# expansion_rxtx_rev_b.net
KiCad netlist of a schematic drawn in EAGLE
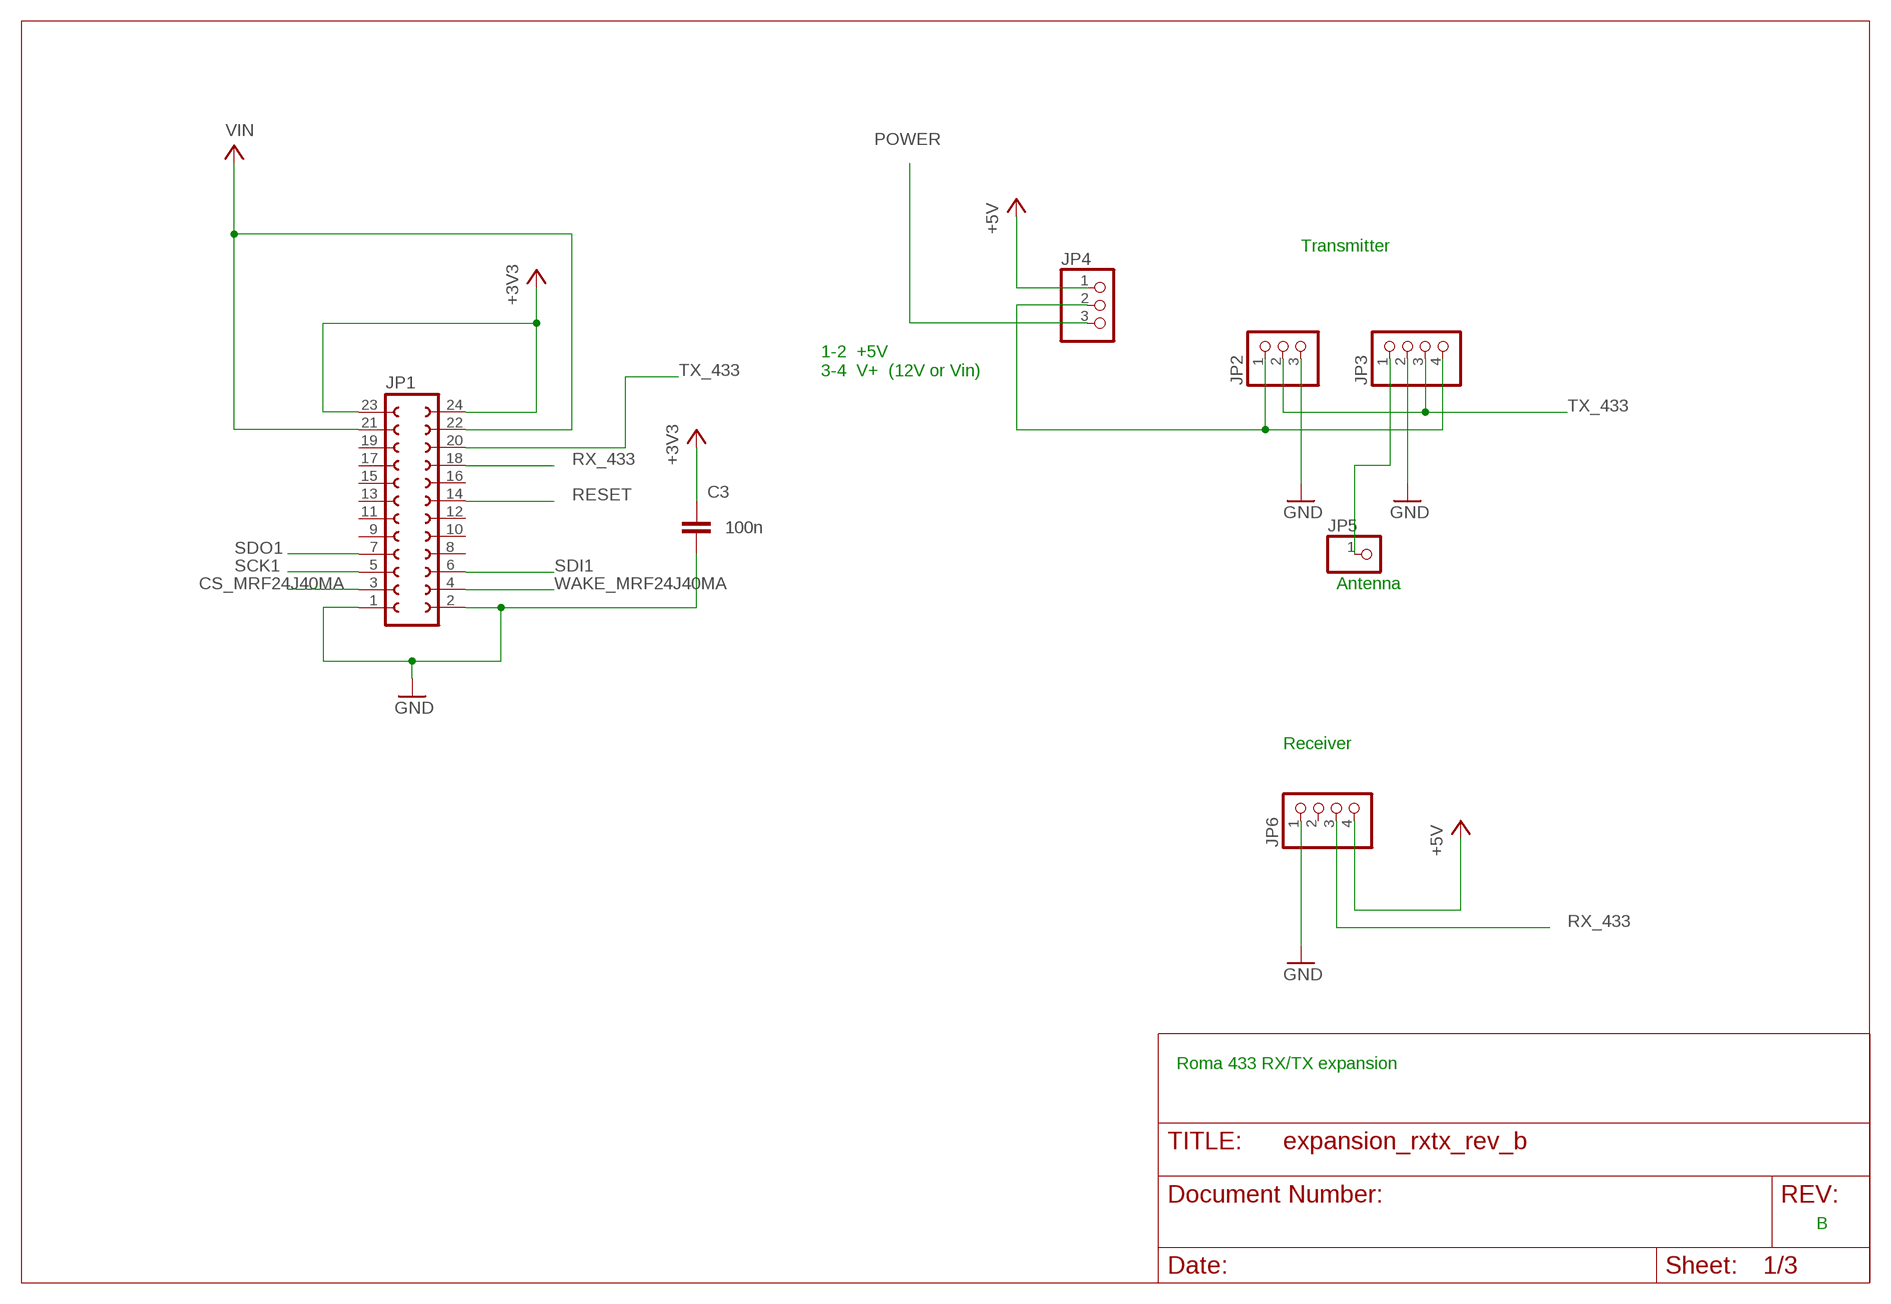
[diagram p0: schematic, sheet 1]
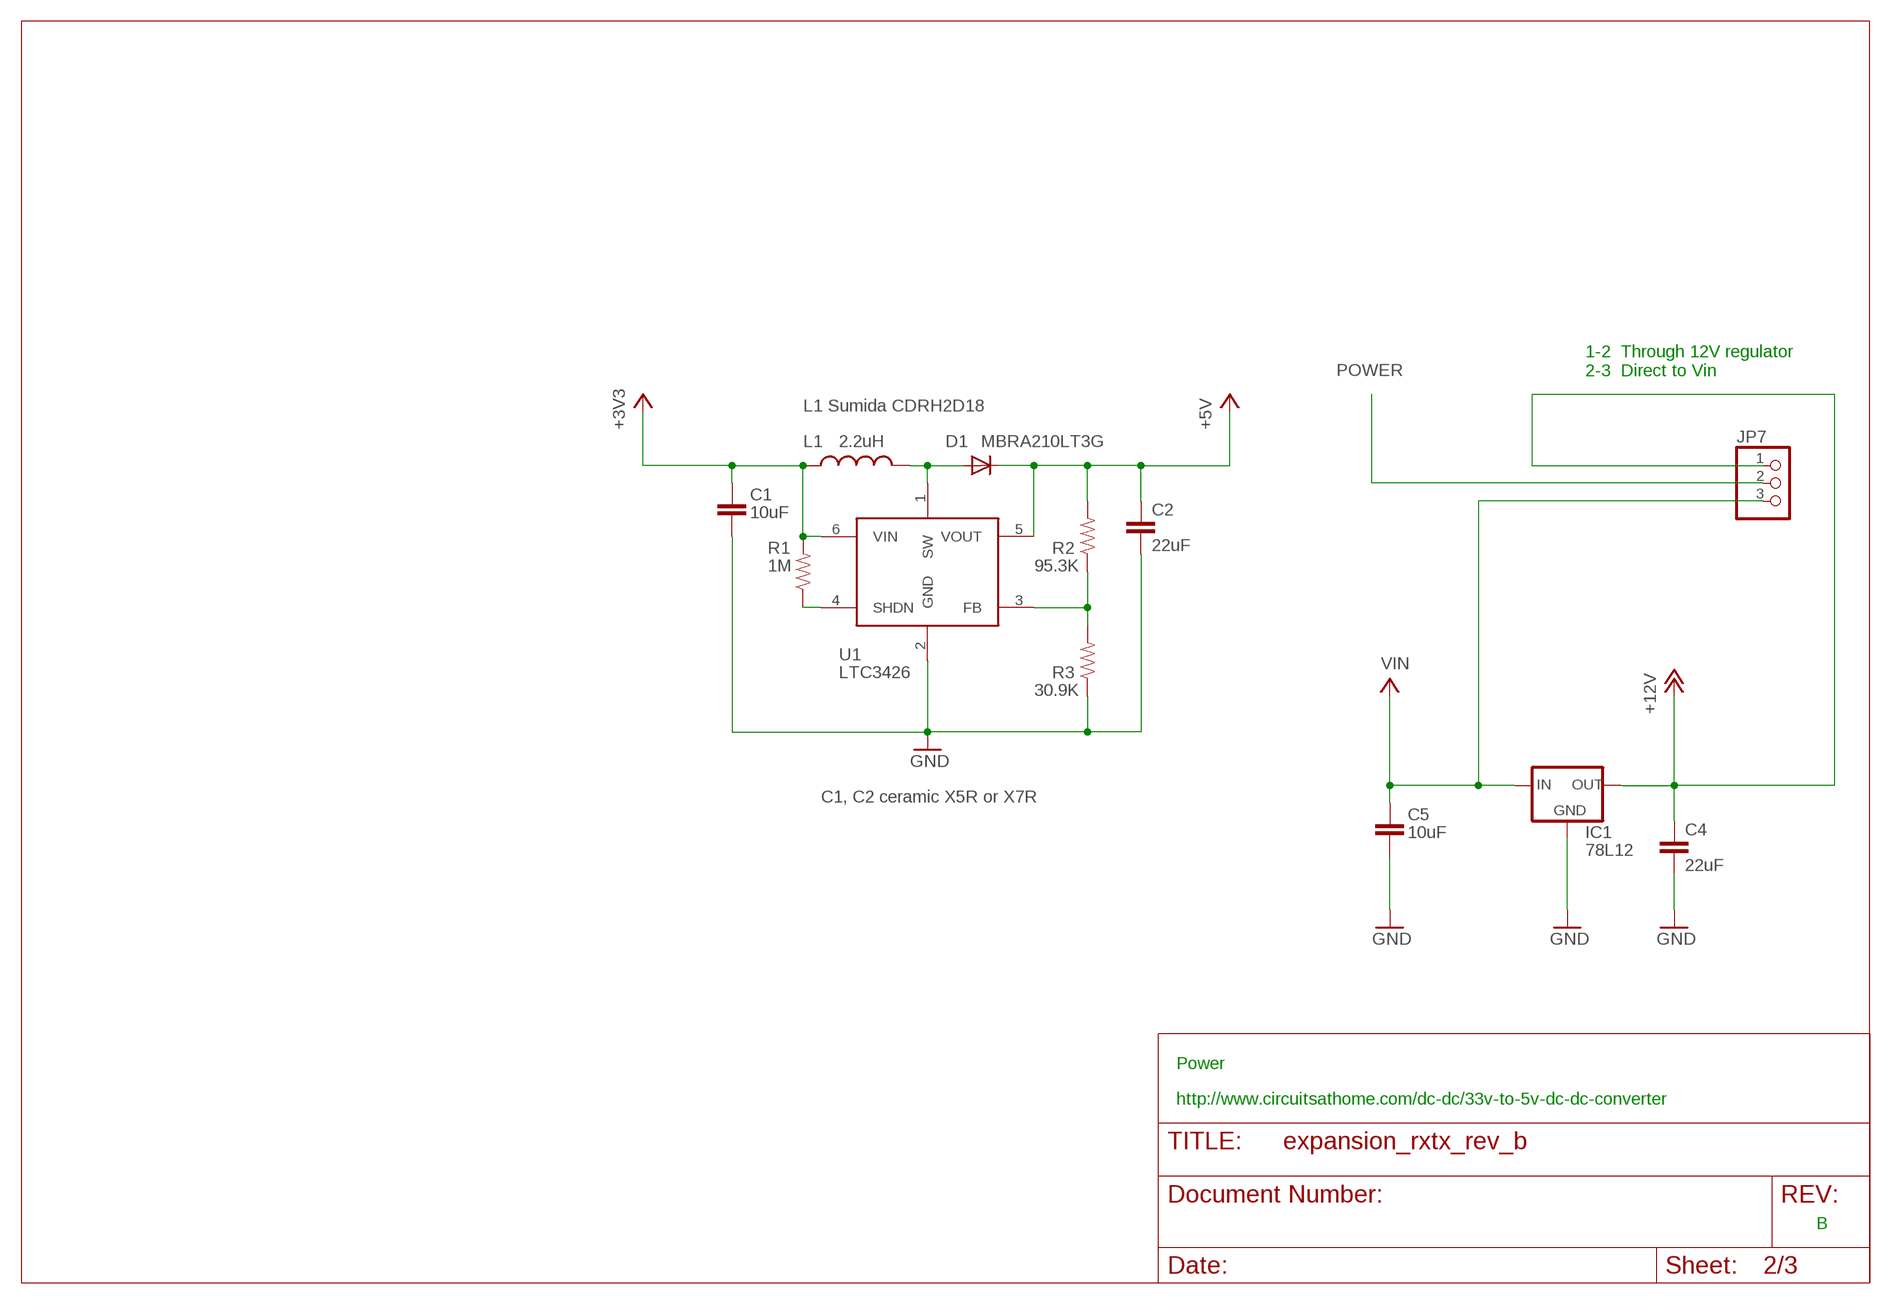
[diagram p1: schematic, sheet 2]
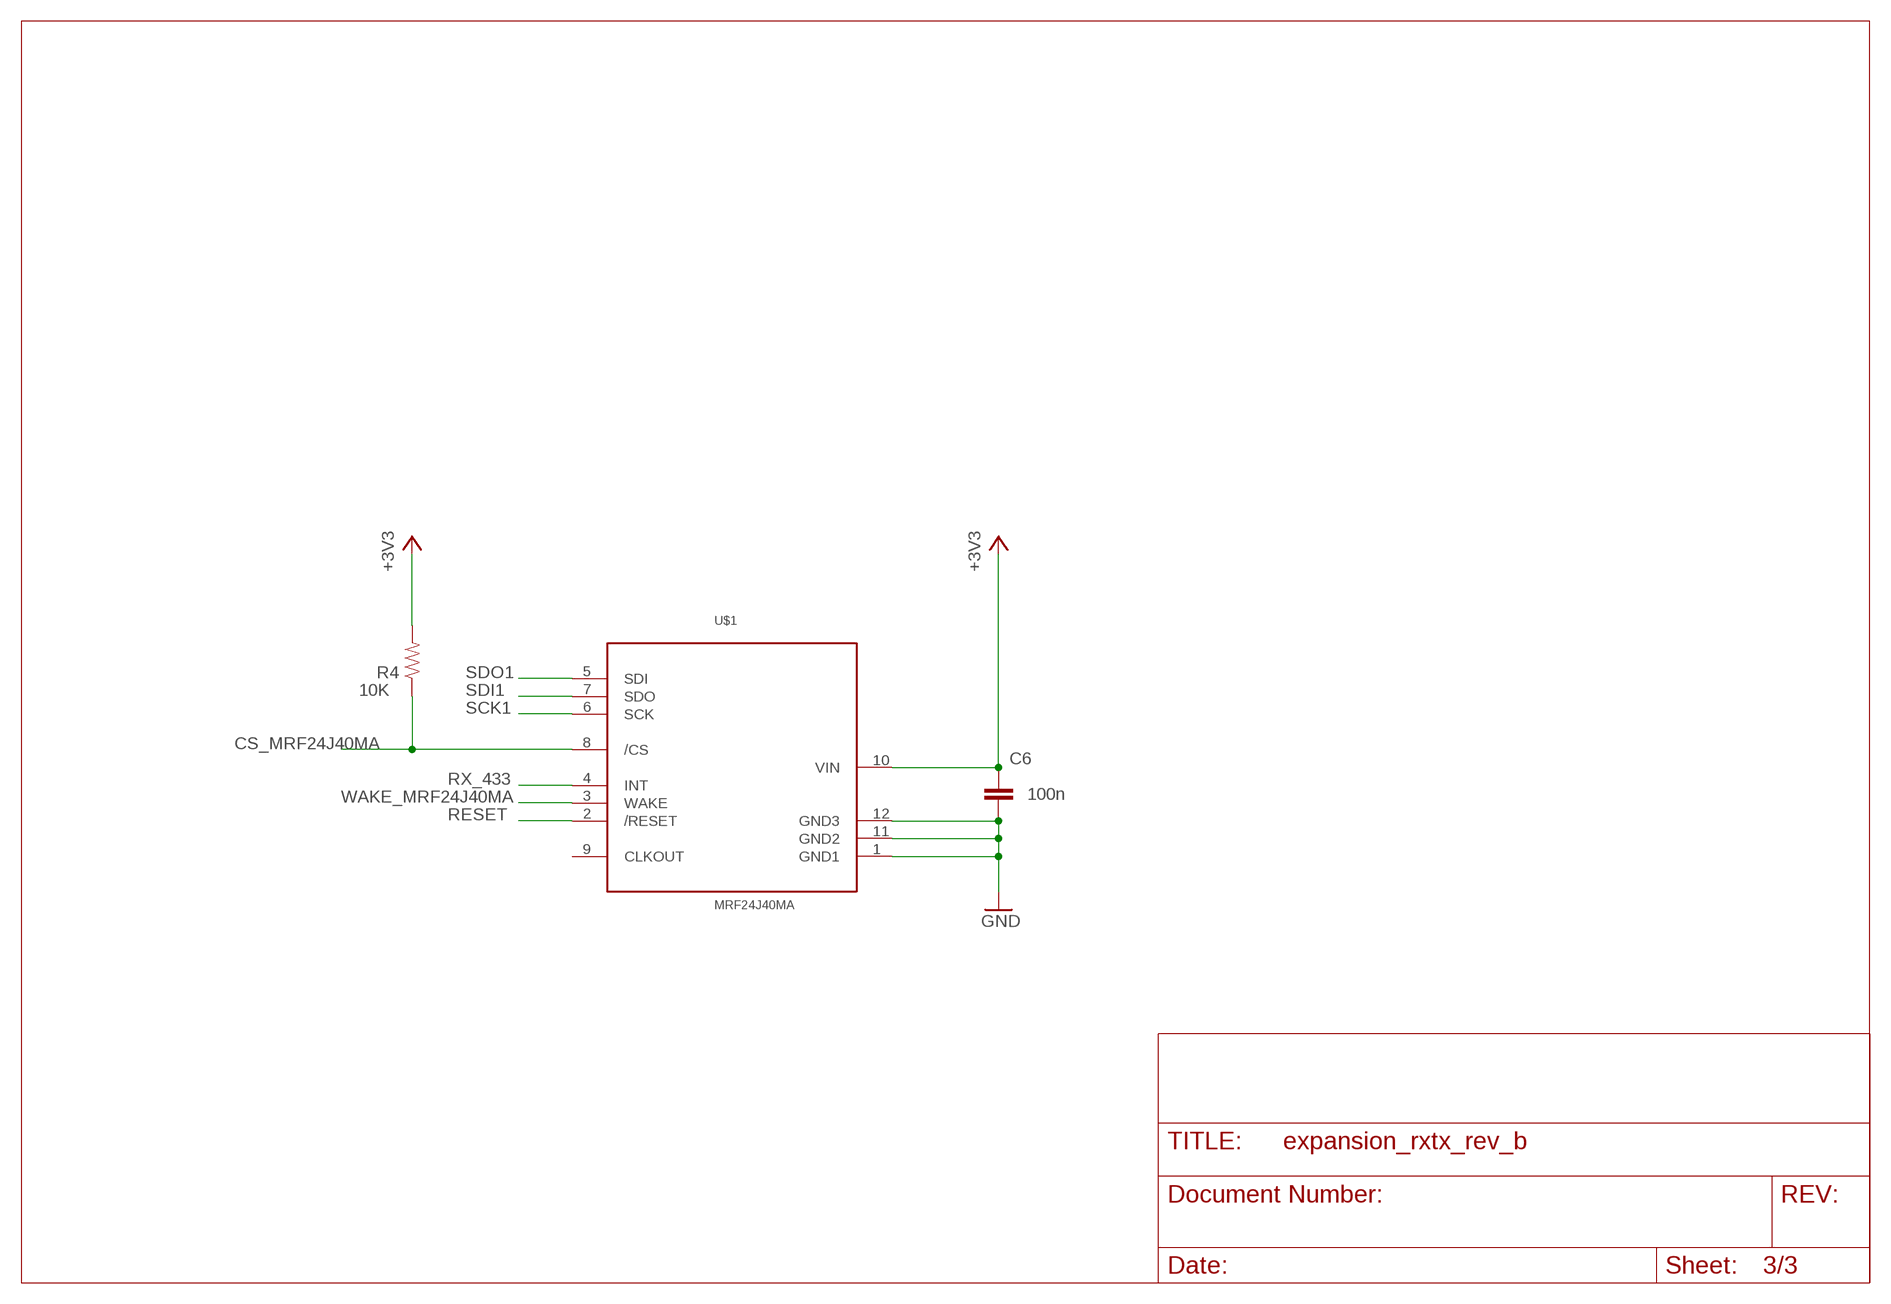
[diagram p2: schematic, sheet 3]

(export (version "E")
  (design (tool "Eeschema 10.0.6"))
  (components
    (comp (ref "C1")
      (value "10uF")
      (footprint "eagle-import:1210")
      (libsource (lib "eagle-import") (part "CAP1210"))
    )
    (comp (ref "C2")
      (value "22uF")
      (footprint "eagle-import:1210")
      (libsource (lib "eagle-import") (part "CAP1210"))
    )
    (comp (ref "C4")
      (value "22uF")
      (footprint "eagle-import:1210")
      (libsource (lib "eagle-import") (part "CAP1210"))
    )
    (comp (ref "C5")
      (value "10uF")
      (footprint "eagle-import:1210")
      (libsource (lib "eagle-import") (part "CAP1210"))
    )
    (comp (ref "D1")
      (value "MBRA210LT3G")
      (footprint "eagle-import:SMA-DIODE")
      (libsource (lib "eagle-import") (part "DIODESMA"))
    )
    (comp (ref "IC1")
      (value "78L12")
      (footprint "eagle-import:78LXX")
      (libsource (lib "eagle-import") (part "78LXX"))
    )
    (comp (ref "JP7")
      (value "PINHD-1X3")
      (footprint "eagle-import:1X03")
      (libsource (lib "eagle-import") (part "PINHD-1X3"))
    )
    (comp (ref "L1")
      (value "2.2uH")
      (footprint "eagle-import:1_3X1_3")
      (libsource (lib "eagle-import") (part "INDUCTOR1313"))
    )
    (comp (ref "R1")
      (value "1M")
      (footprint "eagle-import:0805")
      (libsource (lib "eagle-import") (part "RESISTOR0805"))
    )
    (comp (ref "R2")
      (value "95.3K")
      (footprint "eagle-import:0805")
      (libsource (lib "eagle-import") (part "RESISTOR0805"))
    )
    (comp (ref "R3")
      (value "30.9K")
      (footprint "eagle-import:0805")
      (libsource (lib "eagle-import") (part "RESISTOR0805"))
    )
    (comp (ref "U1")
      (value "LTC3426")
      (footprint "eagle-import:SOT23-6")
      (libsource (lib "eagle-import") (part "LTC3426"))
    )
    (comp (ref "C6")
      (value "100n")
      (footprint "eagle-import:C0805")
      (libsource (lib "eagle-import") (part "C-EUC0805"))
    )
    (comp (ref "R4")
      (value "10K")
      (footprint "eagle-import:0805")
      (libsource (lib "eagle-import") (part "RESISTOR0805"))
    )
    (comp (ref "U$1")
      (value "MRF24J40MA")
      (footprint "eagle-import:MRF24J40MA")
      (libsource (lib "eagle-import") (part "MRF24J40MA"))
    )
    (comp (ref "C3")
      (value "100n")
      (footprint "eagle-import:C0805")
      (libsource (lib "eagle-import") (part "C-EUC0805"))
    )
    (comp (ref "JP1")
      (value "FE12-2")
      (footprint "eagle-import:FE12-2")
      (libsource (lib "eagle-import") (part "FE12-2"))
    )
    (comp (ref "JP2")
      (value "PINHD-1X3")
      (footprint "eagle-import:1X03")
      (libsource (lib "eagle-import") (part "PINHD-1X3"))
    )
    (comp (ref "JP3")
      (value "PINHD-1X4")
      (footprint "eagle-import:1X04")
      (libsource (lib "eagle-import") (part "PINHD-1X4"))
    )
    (comp (ref "JP4")
      (value "PINHD-1X3")
      (footprint "eagle-import:1X03")
      (libsource (lib "eagle-import") (part "PINHD-1X3"))
    )
    (comp (ref "JP5")
      (value "PINHD-1X1")
      (footprint "eagle-import:1X01")
      (libsource (lib "eagle-import") (part "PINHD-1X1"))
    )
    (comp (ref "JP6")
      (value "PINHD-1X4")
      (footprint "eagle-import:1X04")
      (libsource (lib "eagle-import") (part "PINHD-1X4"))
    )
  )
  (nets
    (net (code "1") (name "+3V3") (class "Default")
      (node (ref "C1") (pin "1") (pinfunction "1_1") (pintype "passive"))
      (node (ref "C3") (pin "1") (pinfunction "1_1") (pintype "passive"))
      (node (ref "C6") (pin "1") (pinfunction "1_1") (pintype "passive"))
      (node (ref "JP1") (pin "23") (pinfunction "23_23") (pintype "passive"))
      (node (ref "JP1") (pin "24") (pinfunction "24_24") (pintype "passive"))
      (node (ref "L1") (pin "P$1") (pinfunction "1_P$1") (pintype "passive"))
      (node (ref "R1") (pin "2") (pinfunction "2_2") (pintype "passive"))
      (node (ref "R4") (pin "2") (pinfunction "2_2") (pintype "passive"))
      (node (ref "U$1") (pin "10") (pinfunction "VIN_10") (pintype "power_in"))
      (node (ref "U1") (pin "6") (pinfunction "VIN_6") (pintype "power_in"))
    )
    (net (code "2") (name "+5V") (class "Default")
      (node (ref "C2") (pin "1") (pinfunction "1_1") (pintype "passive"))
      (node (ref "D1") (pin "C") (pinfunction "C_C") (pintype "passive"))
      (node (ref "JP4") (pin "1") (pinfunction "1_1") (pintype "passive"))
      (node (ref "JP6") (pin "4") (pinfunction "4_4") (pintype "passive"))
      (node (ref "R2") (pin "2") (pinfunction "2_2") (pintype "passive"))
      (node (ref "U1") (pin "5") (pinfunction "VOUT_5") (pintype "passive"))
    )
    (net (code "3") (name "+12V") (class "Default")
      (node (ref "C4") (pin "1") (pinfunction "1_1") (pintype "passive"))
      (node (ref "IC1") (pin "OUT") (pinfunction "OUT_OUT") (pintype "passive"))
      (node (ref "JP7") (pin "1") (pinfunction "1_1") (pintype "passive"))
    )
    (net (code "4") (name "CS_MRF24J40MA") (class "Default")
      (node (ref "JP1") (pin "3") (pinfunction "3_3") (pintype "passive"))
      (node (ref "R4") (pin "1") (pinfunction "1_1") (pintype "passive"))
      (node (ref "U$1") (pin "8") (pinfunction "/CS_8") (pintype "bidirectional"))
    )
    (net (code "5") (name "GND") (class "Default")
      (node (ref "C1") (pin "2") (pinfunction "2_2") (pintype "passive"))
      (node (ref "C2") (pin "2") (pinfunction "2_2") (pintype "passive"))
      (node (ref "C3") (pin "2") (pinfunction "2_2") (pintype "passive"))
      (node (ref "C4") (pin "2") (pinfunction "2_2") (pintype "passive"))
      (node (ref "C5") (pin "2") (pinfunction "2_2") (pintype "passive"))
      (node (ref "C6") (pin "2") (pinfunction "2_2") (pintype "passive"))
      (node (ref "IC1") (pin "GND") (pinfunction "GND_GND") (pintype "input"))
      (node (ref "JP1") (pin "1") (pinfunction "1_1") (pintype "passive"))
      (node (ref "JP1") (pin "2") (pinfunction "2_2") (pintype "passive"))
      (node (ref "JP2") (pin "3") (pinfunction "3_3") (pintype "passive"))
      (node (ref "JP3") (pin "2") (pinfunction "2_2") (pintype "passive"))
      (node (ref "JP6") (pin "1") (pinfunction "1_1") (pintype "passive"))
      (node (ref "R3") (pin "1") (pinfunction "1_1") (pintype "passive"))
      (node (ref "U$1") (pin "1") (pinfunction "GND1_1") (pintype "power_in"))
      (node (ref "U$1") (pin "11") (pinfunction "GND2_11") (pintype "power_in"))
      (node (ref "U$1") (pin "12") (pinfunction "GND3_12") (pintype "power_in"))
      (node (ref "U1") (pin "2") (pinfunction "GND_2") (pintype "passive"))
    )
    (net (code "6") (name "Net-(JP2-Pad1)") (class "Default")
      (node (ref "JP2") (pin "1") (pinfunction "1_1") (pintype "passive"))
      (node (ref "JP3") (pin "4") (pinfunction "4_4") (pintype "passive"))
      (node (ref "JP4") (pin "2") (pinfunction "2_2") (pintype "passive"))
    )
    (net (code "7") (name "Net-(JP3-Pad1)") (class "Default")
      (node (ref "JP3") (pin "1") (pinfunction "1_1") (pintype "passive"))
      (node (ref "JP5") (pin "1") (pinfunction "1_1") (pintype "passive"))
    )
    (net (code "8") (name "Net-(L1-2)") (class "Default")
      (node (ref "D1") (pin "A") (pinfunction "A_A") (pintype "passive"))
      (node (ref "L1") (pin "P$2") (pinfunction "2_P$2") (pintype "passive"))
      (node (ref "U1") (pin "1") (pinfunction "SW_1") (pintype "passive"))
    )
    (net (code "9") (name "Net-(U1-FB)") (class "Default")
      (node (ref "R2") (pin "1") (pinfunction "1_1") (pintype "passive"))
      (node (ref "R3") (pin "2") (pinfunction "2_2") (pintype "passive"))
      (node (ref "U1") (pin "3") (pinfunction "FB_3") (pintype "input"))
    )
    (net (code "10") (name "Net-(U1-SHDN)") (class "Default")
      (node (ref "R1") (pin "1") (pinfunction "1_1") (pintype "passive"))
      (node (ref "U1") (pin "4") (pinfunction "SHDN_4") (pintype "input"))
    )
    (net (code "11") (name "POWER") (class "Default")
      (node (ref "JP4") (pin "3") (pinfunction "3_3") (pintype "passive"))
      (node (ref "JP7") (pin "2") (pinfunction "2_2") (pintype "passive"))
    )
    (net (code "12") (name "RESET") (class "Default")
      (node (ref "JP1") (pin "14") (pinfunction "14_14") (pintype "passive"))
      (node (ref "U$1") (pin "2") (pinfunction "/RESET_2") (pintype "bidirectional"))
    )
    (net (code "13") (name "RX_433") (class "Default")
      (node (ref "JP1") (pin "18") (pinfunction "18_18") (pintype "passive"))
      (node (ref "JP6") (pin "3") (pinfunction "3_3") (pintype "passive"))
      (node (ref "U$1") (pin "4") (pinfunction "INT_4") (pintype "bidirectional"))
    )
    (net (code "14") (name "SCK1") (class "Default")
      (node (ref "JP1") (pin "5") (pinfunction "5_5") (pintype "passive"))
      (node (ref "U$1") (pin "6") (pinfunction "SCK_6") (pintype "bidirectional"))
    )
    (net (code "15") (name "SDI1") (class "Default")
      (node (ref "JP1") (pin "6") (pinfunction "6_6") (pintype "passive"))
      (node (ref "U$1") (pin "7") (pinfunction "SDO_7") (pintype "bidirectional"))
    )
    (net (code "16") (name "SDO1") (class "Default")
      (node (ref "JP1") (pin "7") (pinfunction "7_7") (pintype "passive"))
      (node (ref "U$1") (pin "5") (pinfunction "SDI_5") (pintype "bidirectional"))
    )
    (net (code "17") (name "TX_433") (class "Default")
      (node (ref "JP1") (pin "20") (pinfunction "20_20") (pintype "passive"))
      (node (ref "JP2") (pin "2") (pinfunction "2_2") (pintype "passive"))
      (node (ref "JP3") (pin "3") (pinfunction "3_3") (pintype "passive"))
    )
    (net (code "18") (name "VIN") (class "Default")
      (node (ref "C5") (pin "1") (pinfunction "1_1") (pintype "passive"))
      (node (ref "IC1") (pin "IN") (pinfunction "IN_IN") (pintype "input"))
      (node (ref "JP1") (pin "21") (pinfunction "21_21") (pintype "passive"))
      (node (ref "JP1") (pin "22") (pinfunction "22_22") (pintype "passive"))
      (node (ref "JP7") (pin "3") (pinfunction "3_3") (pintype "passive"))
    )
    (net (code "19") (name "WAKE_MRF24J40MA") (class "Default")
      (node (ref "JP1") (pin "4") (pinfunction "4_4") (pintype "passive"))
      (node (ref "U$1") (pin "3") (pinfunction "WAKE_3") (pintype "bidirectional"))
    )
    (net (code "20") (name "unconnected-(JP1-Pad8)") (class "Default")
      (node (ref "JP1") (pin "8") (pinfunction "8_8") (pintype "passive"))
    )
    (net (code "21") (name "unconnected-(JP1-Pad9)") (class "Default")
      (node (ref "JP1") (pin "9") (pinfunction "9_9") (pintype "passive"))
    )
    (net (code "22") (name "unconnected-(JP1-Pad10)") (class "Default")
      (node (ref "JP1") (pin "10") (pinfunction "10_10") (pintype "passive"))
    )
    (net (code "23") (name "unconnected-(JP1-Pad11)") (class "Default")
      (node (ref "JP1") (pin "11") (pinfunction "11_11") (pintype "passive"))
    )
    (net (code "24") (name "unconnected-(JP1-Pad12)") (class "Default")
      (node (ref "JP1") (pin "12") (pinfunction "12_12") (pintype "passive"))
    )
    (net (code "25") (name "unconnected-(JP1-Pad13)") (class "Default")
      (node (ref "JP1") (pin "13") (pinfunction "13_13") (pintype "passive"))
    )
    (net (code "26") (name "unconnected-(JP1-Pad15)") (class "Default")
      (node (ref "JP1") (pin "15") (pinfunction "15_15") (pintype "passive"))
    )
    (net (code "27") (name "unconnected-(JP1-Pad16)") (class "Default")
      (node (ref "JP1") (pin "16") (pinfunction "16_16") (pintype "passive"))
    )
    (net (code "28") (name "unconnected-(JP1-Pad17)") (class "Default")
      (node (ref "JP1") (pin "17") (pinfunction "17_17") (pintype "passive"))
    )
    (net (code "29") (name "unconnected-(JP1-Pad19)") (class "Default")
      (node (ref "JP1") (pin "19") (pinfunction "19_19") (pintype "passive"))
    )
    (net (code "30") (name "unconnected-(JP6-Pad2)") (class "Default")
      (node (ref "JP6") (pin "2") (pinfunction "2_2") (pintype "passive"))
    )
    (net (code "31") (name "unconnected-(U$1-CLKOUT-Pad9)") (class "Default")
      (node (ref "U$1") (pin "9") (pinfunction "CLKOUT_9") (pintype "output"))
    )
  )
)
